# PCB_2_0_4.net
KiCad netlist of a schematic drawn in EAGLE
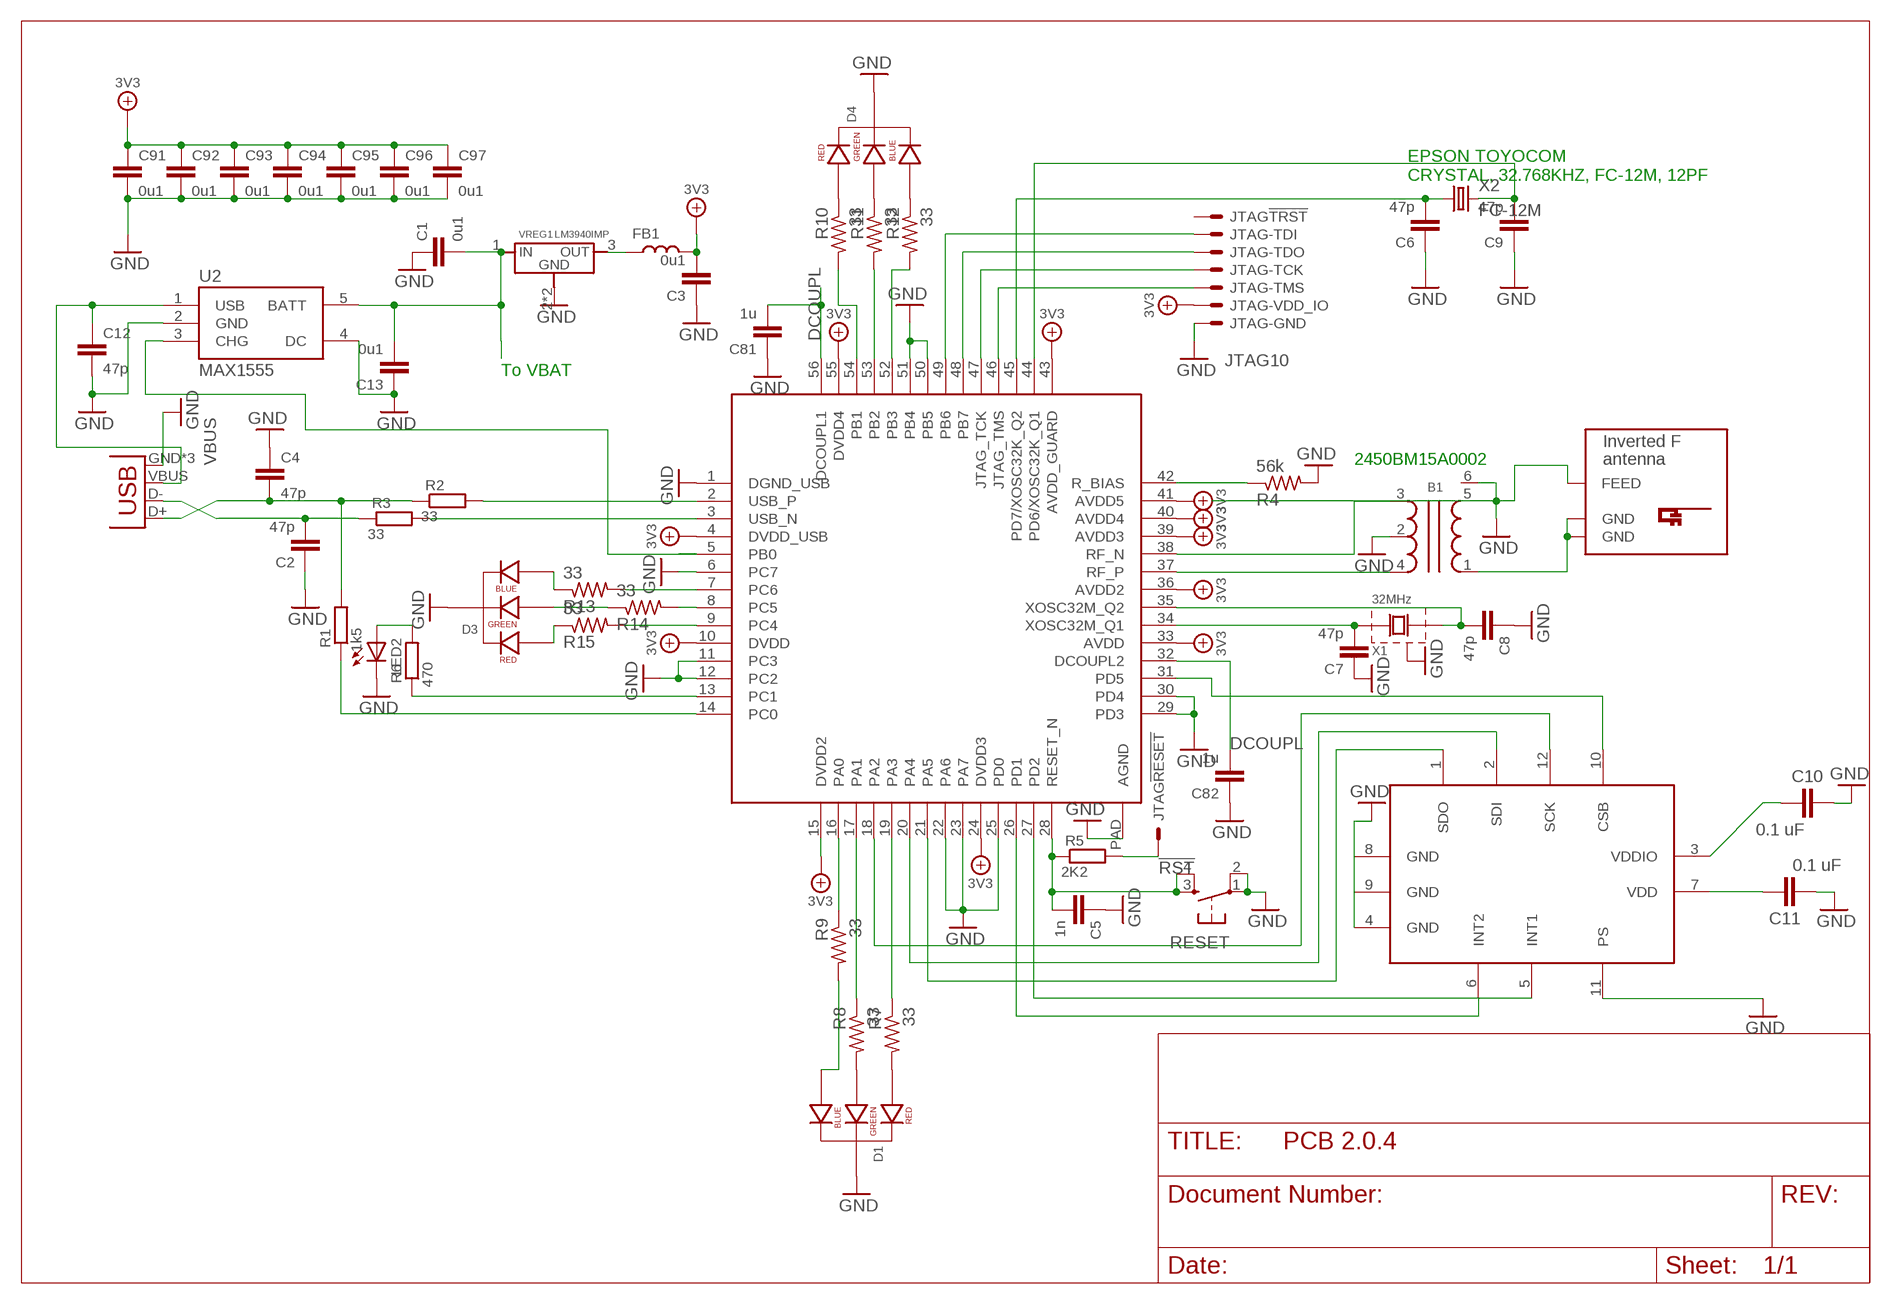
[diagram p0: schematic, sheet 1]

(export (version "E")
  (design (tool "Eeschema 10.0.6"))
  (components
    (comp (ref "B1")
      (value "BALUN")
      (footprint "eagle-import:BALUN-0805")
      (libsource (lib "eagle-import") (part "BALUN"))
    )
    (comp (ref "C1")
      (value "0u1")
      (footprint "eagle-import:C1206")
      (libsource (lib "eagle-import") (part "CC1206"))
    )
    (comp (ref "C2")
      (value "47p")
      (footprint "eagle-import:C0603")
      (libsource (lib "eagle-import") (part "CC0603"))
    )
    (comp (ref "C3")
      (value "0u1")
      (footprint "eagle-import:C1206")
      (libsource (lib "eagle-import") (part "CC1206"))
    )
    (comp (ref "C4")
      (value "47p")
      (footprint "eagle-import:C0603")
      (libsource (lib "eagle-import") (part "CC0603"))
    )
    (comp (ref "C5")
      (value "1n")
      (footprint "eagle-import:C0603")
      (libsource (lib "eagle-import") (part "CC0603"))
    )
    (comp (ref "C6")
      (value "47p")
      (footprint "eagle-import:C0603")
      (libsource (lib "eagle-import") (part "CC0603"))
    )
    (comp (ref "C7")
      (value "47p")
      (footprint "eagle-import:C0603")
      (libsource (lib "eagle-import") (part "CC0603"))
    )
    (comp (ref "C8")
      (value "47p")
      (footprint "eagle-import:C0603")
      (libsource (lib "eagle-import") (part "CC0603"))
    )
    (comp (ref "C9")
      (value "47p")
      (footprint "eagle-import:C0603")
      (libsource (lib "eagle-import") (part "CC0603"))
    )
    (comp (ref "C10")
      (value "0.1 uF")
      (footprint "eagle-import:C0402")
      (libsource (lib "eagle-import") (part "C-EUC0402"))
    )
    (comp (ref "C11")
      (value "0.1 uF")
      (footprint "eagle-import:C0402")
      (libsource (lib "eagle-import") (part "C-EUC0402"))
    )
    (comp (ref "C12")
      (value "47p")
      (footprint "eagle-import:C0603")
      (libsource (lib "eagle-import") (part "CC0603"))
    )
    (comp (ref "C13")
      (value "0u1")
      (footprint "eagle-import:C1206")
      (libsource (lib "eagle-import") (part "CC1206"))
    )
    (comp (ref "C81")
      (value "1u")
      (footprint "eagle-import:C0402")
      (libsource (lib "eagle-import") (part "CC0402"))
    )
    (comp (ref "C82")
      (value "1u")
      (footprint "eagle-import:C0402")
      (libsource (lib "eagle-import") (part "CC0402"))
    )
    (comp (ref "C91")
      (value "0u1")
      (footprint "eagle-import:C0402")
      (libsource (lib "eagle-import") (part "CC0402"))
    )
    (comp (ref "C92")
      (value "0u1")
      (footprint "eagle-import:C0402")
      (libsource (lib "eagle-import") (part "CC0402"))
    )
    (comp (ref "C93")
      (value "0u1")
      (footprint "eagle-import:C0402")
      (libsource (lib "eagle-import") (part "CC0402"))
    )
    (comp (ref "C94")
      (value "0u1")
      (footprint "eagle-import:C0402")
      (libsource (lib "eagle-import") (part "CC0402"))
    )
    (comp (ref "C95")
      (value "0u1")
      (footprint "eagle-import:C0402")
      (libsource (lib "eagle-import") (part "CC0402"))
    )
    (comp (ref "C96")
      (value "0u1")
      (footprint "eagle-import:C0402")
      (libsource (lib "eagle-import") (part "CC0402"))
    )
    (comp (ref "C97")
      (value "0u1")
      (footprint "eagle-import:C0402")
      (libsource (lib "eagle-import") (part "CC0402"))
    )
    (comp (ref "D1")
      (value "LED-RGB-CC-THRUCLEAR")
      (footprint "eagle-import:LED-RGB-THRU")
      (libsource (lib "eagle-import") (part "LED-RGB-CC-THRUCLEAR"))
    )
    (comp (ref "D3")
      (value "LED-RGB-CC-THRUCLEAR")
      (footprint "eagle-import:LED-RGB-THRU")
      (libsource (lib "eagle-import") (part "LED-RGB-CC-THRUCLEAR"))
    )
    (comp (ref "D4")
      (value "LED-RGB-CC-THRUCLEAR")
      (footprint "eagle-import:LED-RGB-THRU")
      (libsource (lib "eagle-import") (part "LED-RGB-CC-THRUCLEAR"))
    )
    (comp (ref "FB1")
      (value "L0603")
      (footprint "eagle-import:R603")
      (libsource (lib "eagle-import") (part "L0603"))
    )
    (comp (ref "JP1")
      (value "USB-MICROB")
      (footprint "eagle-import:USB-MICROB")
      (libsource (lib "eagle-import") (part "USB-MICROB"))
    )
    (comp (ref "JTAG")
      (value "JTAG10")
      (footprint "eagle-import:HDR-2X5-2.00")
      (libsource (lib "eagle-import") (part "JTAG10"))
    )
    (comp (ref "LED2")
      (value "LED805")
      (footprint "eagle-import:LED-805")
      (libsource (lib "eagle-import") (part "LED805"))
    )
    (comp (ref "R1")
      (value "1k5")
      (footprint "eagle-import:R603")
      (libsource (lib "eagle-import") (part "RR603"))
    )
    (comp (ref "R2")
      (value "33")
      (footprint "eagle-import:R603")
      (libsource (lib "eagle-import") (part "RR603"))
    )
    (comp (ref "R3")
      (value "33")
      (footprint "eagle-import:R603")
      (libsource (lib "eagle-import") (part "RR603"))
    )
    (comp (ref "R4")
      (value "56k")
      (footprint "eagle-import:R0402")
      (libsource (lib "eagle-import") (part "R-US_R0402"))
    )
    (comp (ref "R5")
      (value "2K2")
      (footprint "eagle-import:R603")
      (libsource (lib "eagle-import") (part "RR603"))
    )
    (comp (ref "R6")
      (value "470")
      (footprint "eagle-import:R603")
      (libsource (lib "eagle-import") (part "RR603"))
    )
    (comp (ref "R7")
      (value "33")
      (footprint "eagle-import:R0402")
      (libsource (lib "eagle-import") (part "R-US_R0402"))
    )
    (comp (ref "R8")
      (value "33")
      (footprint "eagle-import:R0402")
      (libsource (lib "eagle-import") (part "R-US_R0402"))
    )
    (comp (ref "R9")
      (value "33")
      (footprint "eagle-import:R0402")
      (libsource (lib "eagle-import") (part "R-US_R0402"))
    )
    (comp (ref "R10")
      (value "33")
      (footprint "eagle-import:R0402")
      (libsource (lib "eagle-import") (part "R-US_R0402"))
    )
    (comp (ref "R11")
      (value "33")
      (footprint "eagle-import:R0402")
      (libsource (lib "eagle-import") (part "R-US_R0402"))
    )
    (comp (ref "R12")
      (value "33")
      (footprint "eagle-import:R0402")
      (libsource (lib "eagle-import") (part "R-US_R0402"))
    )
    (comp (ref "R13")
      (value "33")
      (footprint "eagle-import:R0402")
      (libsource (lib "eagle-import") (part "R-US_R0402"))
    )
    (comp (ref "R14")
      (value "33")
      (footprint "eagle-import:R0402")
      (libsource (lib "eagle-import") (part "R-US_R0402"))
    )
    (comp (ref "R15")
      (value "33")
      (footprint "eagle-import:R0402")
      (libsource (lib "eagle-import") (part "R-US_R0402"))
    )
    (comp (ref "RESET")
      (value "TAC_SWITCHSMD")
      (footprint "eagle-import:TACTILE_SWITCH_SMD")
      (libsource (lib "eagle-import") (part "TAC_SWITCHSMD"))
    )
    (comp (ref "U$1")
      (value "BMA250")
      (footprint "eagle-import:12LGA_VGG3-D")
      (libsource (lib "eagle-import") (part "BMA250"))
    )
    (comp (ref "U$2")
      (value "INVERTED_F_ANTENNA+0")
      (footprint "eagle-import:DN007+0")
      (libsource (lib "eagle-import") (part "INVERTED_F_ANTENNA+0"))
    )
    (comp (ref "U1")
      (value "CC2538")
      (footprint "eagle-import:QFN56")
      (libsource (lib "eagle-import") (part "CC2538"))
    )
    (comp (ref "U2")
      (value "MAX1555")
      (footprint "eagle-import:SOT23-5")
      (libsource (lib "eagle-import") (part "MAX1555"))
    )
    (comp (ref "VREG1")
      (value "LM3940IMP")
      (footprint "eagle-import:SOT223")
      (libsource (lib "eagle-import") (part "LM3940IMP"))
    )
    (comp (ref "X1")
      (value "32MHz")
      (footprint "eagle-import:XTAL-4-3225")
      (libsource (lib "eagle-import") (part "XTAL-43225"))
    )
    (comp (ref "X2")
      (value "FC-12M")
      (footprint "eagle-import:FC-12M")
      (libsource (lib "eagle-import") (part "FC-12M"))
    )
  )
  (nets
    (net (code "1") (name "/DCOUPL") (class "Default")
      (node (ref "C81") (pin "2") (pinfunction "2_2") (pintype "passive"))
      (node (ref "C82") (pin "2") (pinfunction "2_2") (pintype "passive"))
      (node (ref "U1") (pin "32") (pinfunction "DCOUPL2_32") (pintype "bidirectional"))
      (node (ref "U1") (pin "56") (pinfunction "DCOUPL1_56") (pintype "bidirectional"))
    )
    (net (code "2") (name "/VBUS") (class "Default")
      (node (ref "C12") (pin "1") (pinfunction "1_1") (pintype "passive"))
      (node (ref "JP1") (pin "VBUS") (pinfunction "VBUS_VBUS") (pintype "bidirectional"))
      (node (ref "U2") (pin "1") (pinfunction "USB_1") (pintype "bidirectional"))
    )
    (net (code "3") (name "/~{RST}") (class "Default")
      (node (ref "JTAG") (pin "4") (pinfunction "S_4") (pintype "passive"))
      (node (ref "R5") (pin "2") (pinfunction "2_2") (pintype "passive"))
    )
    (net (code "4") (name "3V3") (class "Default")
      (node (ref "C3") (pin "2") (pinfunction "2_2") (pintype "passive"))
      (node (ref "C91") (pin "1") (pinfunction "1_1") (pintype "passive"))
      (node (ref "C92") (pin "1") (pinfunction "1_1") (pintype "passive"))
      (node (ref "C93") (pin "1") (pinfunction "1_1") (pintype "passive"))
      (node (ref "C94") (pin "1") (pinfunction "1_1") (pintype "passive"))
      (node (ref "C95") (pin "1") (pinfunction "1_1") (pintype "passive"))
      (node (ref "C96") (pin "1") (pinfunction "1_1") (pintype "passive"))
      (node (ref "C97") (pin "1") (pinfunction "1_1") (pintype "passive"))
      (node (ref "FB1") (pin "2") (pinfunction "P$2_2") (pintype "bidirectional"))
      (node (ref "JTAG") (pin "1") (pinfunction "S_1") (pintype "passive"))
      (node (ref "JTAG") (pin "2") (pinfunction "S_2") (pintype "passive"))
      (node (ref "U1") (pin "10") (pinfunction "DVDD_10") (pintype "bidirectional"))
      (node (ref "U1") (pin "15") (pinfunction "DVDD2_15") (pintype "bidirectional"))
      (node (ref "U1") (pin "24") (pinfunction "DVDD3_24") (pintype "bidirectional"))
      (node (ref "U1") (pin "33") (pinfunction "AVDD_33") (pintype "bidirectional"))
      (node (ref "U1") (pin "36") (pinfunction "AVDD2_36") (pintype "bidirectional"))
      (node (ref "U1") (pin "39") (pinfunction "AVDD3_39") (pintype "bidirectional"))
      (node (ref "U1") (pin "4") (pinfunction "DVDD_USB_4") (pintype "bidirectional"))
      (node (ref "U1") (pin "40") (pinfunction "AVDD4_40") (pintype "bidirectional"))
      (node (ref "U1") (pin "41") (pinfunction "AVDD5_41") (pintype "bidirectional"))
      (node (ref "U1") (pin "43") (pinfunction "AVDD_GUARD_43") (pintype "bidirectional"))
      (node (ref "U1") (pin "55") (pinfunction "DVDD4_55") (pintype "bidirectional"))
    )
    (net (code "5") (name "GND") (class "Default")
      (node (ref "B1") (pin "2") (pinfunction "2_2") (pintype "bidirectional"))
      (node (ref "B1") (pin "5") (pinfunction "5_5") (pintype "bidirectional"))
      (node (ref "B1") (pin "6") (pinfunction "6_6") (pintype "bidirectional"))
      (node (ref "C1") (pin "1") (pinfunction "1_1") (pintype "passive"))
      (node (ref "C10") (pin "1") (pinfunction "1_1") (pintype "passive"))
      (node (ref "C11") (pin "2") (pinfunction "2_2") (pintype "passive"))
      (node (ref "C12") (pin "2") (pinfunction "2_2") (pintype "passive"))
      (node (ref "C13") (pin "1") (pinfunction "1_1") (pintype "passive"))
      (node (ref "C2") (pin "1") (pinfunction "1_1") (pintype "passive"))
      (node (ref "C3") (pin "1") (pinfunction "1_1") (pintype "passive"))
      (node (ref "C4") (pin "1") (pinfunction "1_1") (pintype "passive"))
      (node (ref "C5") (pin "1") (pinfunction "1_1") (pintype "passive"))
      (node (ref "C6") (pin "1") (pinfunction "1_1") (pintype "passive"))
      (node (ref "C7") (pin "1") (pinfunction "1_1") (pintype "passive"))
      (node (ref "C8") (pin "1") (pinfunction "1_1") (pintype "passive"))
      (node (ref "C81") (pin "1") (pinfunction "1_1") (pintype "passive"))
      (node (ref "C82") (pin "1") (pinfunction "1_1") (pintype "passive"))
      (node (ref "C9") (pin "1") (pinfunction "1_1") (pintype "passive"))
      (node (ref "C91") (pin "2") (pinfunction "2_2") (pintype "passive"))
      (node (ref "C92") (pin "2") (pinfunction "2_2") (pintype "passive"))
      (node (ref "C93") (pin "2") (pinfunction "2_2") (pintype "passive"))
      (node (ref "C94") (pin "2") (pinfunction "2_2") (pintype "passive"))
      (node (ref "C95") (pin "2") (pinfunction "2_2") (pintype "passive"))
      (node (ref "C96") (pin "2") (pinfunction "2_2") (pintype "passive"))
      (node (ref "C97") (pin "2") (pinfunction "2_2") (pintype "passive"))
      (node (ref "D1") (pin "2") (pinfunction "CATHODE_2") (pintype "bidirectional"))
      (node (ref "D3") (pin "2") (pinfunction "CATHODE_2") (pintype "bidirectional"))
      (node (ref "D4") (pin "2") (pinfunction "CATHODE_2") (pintype "bidirectional"))
      (node (ref "JP1") (pin "GND") (pinfunction "GND_GND") (pintype "bidirectional"))
      (node (ref "JP1") (pin "MT1") (pinfunction "GND_MT1") (pintype "bidirectional"))
      (node (ref "JP1") (pin "MT2") (pinfunction "GND_MT2") (pintype "bidirectional"))
      (node (ref "JTAG") (pin "10") (pinfunction "S_10") (pintype "passive"))
      (node (ref "JTAG") (pin "8") (pinfunction "S_8") (pintype "passive"))
      (node (ref "LED2") (pin "C") (pinfunction "C_C") (pintype "passive"))
      (node (ref "R4") (pin "2") (pinfunction "2_2") (pintype "passive"))
      (node (ref "RESET") (pin "1") (pinfunction "1_1") (pintype "passive"))
      (node (ref "RESET") (pin "2") (pinfunction "2_2") (pintype "passive"))
      (node (ref "U$1") (pin "11") (pinfunction "PS_11") (pintype "bidirectional"))
      (node (ref "U$1") (pin "4") (pinfunction "GND_4") (pintype "bidirectional"))
      (node (ref "U$1") (pin "8") (pinfunction "GND_8") (pintype "bidirectional"))
      (node (ref "U$1") (pin "9") (pinfunction "GND_9") (pintype "bidirectional"))
      (node (ref "U$2") (pin "FEED") (pinfunction "FEED_FEED") (pintype "bidirectional"))
      (node (ref "U1") (pin "1") (pinfunction "DGND_USB_1") (pintype "bidirectional"))
      (node (ref "U1") (pin "11") (pinfunction "PC3_11") (pintype "bidirectional"))
      (node (ref "U1") (pin "12") (pinfunction "PC2_12") (pintype "bidirectional"))
      (node (ref "U1") (pin "22") (pinfunction "PA6_22") (pintype "bidirectional"))
      (node (ref "U1") (pin "23") (pinfunction "PA7_23") (pintype "bidirectional"))
      (node (ref "U1") (pin "25") (pinfunction "PD0_25") (pintype "bidirectional"))
      (node (ref "U1") (pin "29") (pinfunction "PD3_29") (pintype "bidirectional"))
      (node (ref "U1") (pin "30") (pinfunction "PD4_30") (pintype "bidirectional"))
      (node (ref "U1") (pin "50") (pinfunction "PB5_50") (pintype "bidirectional"))
      (node (ref "U1") (pin "51") (pinfunction "PB4_51") (pintype "bidirectional"))
      (node (ref "U1") (pin "6") (pinfunction "PC7_6") (pintype "bidirectional"))
      (node (ref "U1") (pin "PAD") (pinfunction "AGND_PAD") (pintype "bidirectional"))
      (node (ref "U2") (pin "2") (pinfunction "GND_2") (pintype "bidirectional"))
      (node (ref "U2") (pin "4") (pinfunction "DC_4") (pintype "bidirectional"))
      (node (ref "VREG1") (pin "2") (pinfunction "GND_2") (pintype "bidirectional"))
      (node (ref "VREG1") (pin "4") (pinfunction "GND_4") (pintype "bidirectional"))
      (node (ref "X1") (pin "2") (pinfunction "GND1_2") (pintype "bidirectional"))
      (node (ref "X1") (pin "4") (pinfunction "GND1_4") (pintype "bidirectional"))
    )
    (net (code "6") (name "Net-(B1-Pad1)") (class "Default")
      (node (ref "B1") (pin "1") (pinfunction "1_1") (pintype "bidirectional"))
      (node (ref "U$2") (pin "GND") (pinfunction "GND_GND") (pintype "bidirectional"))
      (node (ref "U$2") (pin "GND@1") (pinfunction "GND_GND@1") (pintype "bidirectional"))
    )
    (net (code "7") (name "Net-(C2-Pad2)") (class "Default")
      (node (ref "C2") (pin "2") (pinfunction "2_2") (pintype "passive"))
      (node (ref "JP1") (pin "D-") (pinfunction "D-_D-") (pintype "bidirectional"))
      (node (ref "R3") (pin "1") (pinfunction "1_1") (pintype "passive"))
    )
    (net (code "8") (name "Net-(C4-Pad2)") (class "Default")
      (node (ref "C4") (pin "2") (pinfunction "2_2") (pintype "passive"))
      (node (ref "JP1") (pin "D+") (pinfunction "D+_D+") (pintype "bidirectional"))
      (node (ref "R1") (pin "2") (pinfunction "2_2") (pintype "passive"))
      (node (ref "R2") (pin "1") (pinfunction "1_1") (pintype "passive"))
    )
    (net (code "9") (name "Net-(D1-BLUE_CATHODE)") (class "Default")
      (node (ref "D1") (pin "4") (pinfunction "BLUE_CATHODE_4") (pintype "bidirectional"))
      (node (ref "R9") (pin "2") (pinfunction "2_2") (pintype "passive"))
    )
    (net (code "10") (name "Net-(D1-GREEN_CATHODE)") (class "Default")
      (node (ref "D1") (pin "3") (pinfunction "GREEN_CATHODE_3") (pintype "bidirectional"))
      (node (ref "R8") (pin "2") (pinfunction "2_2") (pintype "passive"))
    )
    (net (code "11") (name "Net-(D1-RED_CATHODE)") (class "Default")
      (node (ref "D1") (pin "1") (pinfunction "RED_CATHODE_1") (pintype "bidirectional"))
      (node (ref "R7") (pin "2") (pinfunction "2_2") (pintype "passive"))
    )
    (net (code "12") (name "Net-(D3-BLUE_CATHODE)") (class "Default")
      (node (ref "D3") (pin "4") (pinfunction "BLUE_CATHODE_4") (pintype "bidirectional"))
      (node (ref "R13") (pin "1") (pinfunction "1_1") (pintype "passive"))
    )
    (net (code "13") (name "Net-(D3-GREEN_CATHODE)") (class "Default")
      (node (ref "D3") (pin "3") (pinfunction "GREEN_CATHODE_3") (pintype "bidirectional"))
      (node (ref "R14") (pin "1") (pinfunction "1_1") (pintype "passive"))
    )
    (net (code "14") (name "Net-(D3-RED_CATHODE)") (class "Default")
      (node (ref "D3") (pin "1") (pinfunction "RED_CATHODE_1") (pintype "bidirectional"))
      (node (ref "R15") (pin "1") (pinfunction "1_1") (pintype "passive"))
    )
    (net (code "15") (name "Net-(D4-BLUE_CATHODE)") (class "Default")
      (node (ref "D4") (pin "4") (pinfunction "BLUE_CATHODE_4") (pintype "bidirectional"))
      (node (ref "R12") (pin "1") (pinfunction "1_1") (pintype "passive"))
    )
    (net (code "16") (name "Net-(D4-GREEN_CATHODE)") (class "Default")
      (node (ref "D4") (pin "3") (pinfunction "GREEN_CATHODE_3") (pintype "bidirectional"))
      (node (ref "R11") (pin "1") (pinfunction "1_1") (pintype "passive"))
    )
    (net (code "17") (name "Net-(D4-RED_CATHODE)") (class "Default")
      (node (ref "D4") (pin "1") (pinfunction "RED_CATHODE_1") (pintype "bidirectional"))
      (node (ref "R10") (pin "1") (pinfunction "1_1") (pintype "passive"))
    )
    (net (code "18") (name "Net-(FB1-P$1)") (class "Default")
      (node (ref "FB1") (pin "1") (pinfunction "P$1_1") (pintype "bidirectional"))
      (node (ref "VREG1") (pin "3") (pinfunction "OUT_3") (pintype "bidirectional"))
    )
    (net (code "19") (name "Net-(JTAGD-S)") (class "Default")
      (node (ref "JTAG") (pin "9") (pinfunction "S_9") (pintype "passive"))
      (node (ref "U1") (pin "47") (pinfunction "JTAG_TCK_47") (pintype "bidirectional"))
    )
    (net (code "20") (name "Net-(JTAGE-S)") (class "Default")
      (node (ref "JTAG") (pin "5") (pinfunction "S_5") (pintype "passive"))
      (node (ref "U1") (pin "49") (pinfunction "PB6_49") (pintype "bidirectional"))
    )
    (net (code "21") (name "Net-(JTAGF-S)") (class "Default")
      (node (ref "JTAG") (pin "6") (pinfunction "S_6") (pintype "passive"))
      (node (ref "U1") (pin "48") (pinfunction "PB7_48") (pintype "bidirectional"))
    )
    (net (code "22") (name "Net-(JTAGG-S)") (class "Default")
      (node (ref "JTAG") (pin "7") (pinfunction "S_7") (pintype "passive"))
      (node (ref "U1") (pin "46") (pinfunction "JTAG_TMS_46") (pintype "bidirectional"))
    )
    (net (code "23") (name "Net-(LED2-PadA)") (class "Default")
      (node (ref "LED2") (pin "A") (pinfunction "A_A") (pintype "passive"))
      (node (ref "R6") (pin "2") (pinfunction "2_2") (pintype "passive"))
    )
    (net (code "24") (name "Net-(U$1-CSB)") (class "Default")
      (node (ref "U$1") (pin "10") (pinfunction "CSB_10") (pintype "bidirectional"))
      (node (ref "U1") (pin "31") (pinfunction "PD5_31") (pintype "bidirectional"))
    )
    (net (code "25") (name "Net-(U$1-INT1)") (class "Default")
      (node (ref "U$1") (pin "5") (pinfunction "INT1_5") (pintype "bidirectional"))
      (node (ref "U1") (pin "27") (pinfunction "PD2_27") (pintype "bidirectional"))
    )
    (net (code "26") (name "Net-(U$1-INT2)") (class "Default")
      (node (ref "U$1") (pin "6") (pinfunction "INT2_6") (pintype "bidirectional"))
      (node (ref "U1") (pin "26") (pinfunction "PD1_26") (pintype "bidirectional"))
    )
    (net (code "27") (name "Net-(U$1-SCK)") (class "Default")
      (node (ref "U$1") (pin "12") (pinfunction "SCK_12") (pintype "bidirectional"))
      (node (ref "U1") (pin "18") (pinfunction "PA2_18") (pintype "bidirectional"))
    )
    (net (code "28") (name "Net-(U$1-SDI)") (class "Default")
      (node (ref "U$1") (pin "2") (pinfunction "SDI_2") (pintype "bidirectional"))
      (node (ref "U1") (pin "20") (pinfunction "PA4_20") (pintype "bidirectional"))
    )
    (net (code "29") (name "Net-(U$1-SDO)") (class "Default")
      (node (ref "U$1") (pin "1") (pinfunction "SDO_1") (pintype "bidirectional"))
      (node (ref "U1") (pin "21") (pinfunction "PA5_21") (pintype "bidirectional"))
    )
    (net (code "30") (name "Net-(U$1-VDD)") (class "Default")
      (node (ref "C11") (pin "1") (pinfunction "1_1") (pintype "passive"))
      (node (ref "U$1") (pin "7") (pinfunction "VDD_7") (pintype "bidirectional"))
    )
    (net (code "31") (name "Net-(U$1-VDDIO)") (class "Default")
      (node (ref "C10") (pin "2") (pinfunction "2_2") (pintype "passive"))
      (node (ref "U$1") (pin "3") (pinfunction "VDDIO_3") (pintype "bidirectional"))
    )
    (net (code "32") (name "Net-(U1-PA0)") (class "Default")
      (node (ref "R9") (pin "1") (pinfunction "1_1") (pintype "passive"))
      (node (ref "U1") (pin "16") (pinfunction "PA0_16") (pintype "bidirectional"))
    )
    (net (code "33") (name "Net-(U1-PA1)") (class "Default")
      (node (ref "R8") (pin "1") (pinfunction "1_1") (pintype "passive"))
      (node (ref "U1") (pin "17") (pinfunction "PA1_17") (pintype "bidirectional"))
    )
    (net (code "34") (name "Net-(U1-PA3)") (class "Default")
      (node (ref "R7") (pin "1") (pinfunction "1_1") (pintype "passive"))
      (node (ref "U1") (pin "19") (pinfunction "PA3_19") (pintype "bidirectional"))
    )
    (net (code "35") (name "Net-(U1-PB0)") (class "Default")
      (node (ref "U1") (pin "5") (pinfunction "PB0_5") (pintype "bidirectional"))
      (node (ref "U2") (pin "3") (pinfunction "CHG_3") (pintype "bidirectional"))
    )
    (net (code "36") (name "Net-(U1-PB1)") (class "Default")
      (node (ref "R10") (pin "2") (pinfunction "2_2") (pintype "passive"))
      (node (ref "U1") (pin "54") (pinfunction "PB1_54") (pintype "bidirectional"))
    )
    (net (code "37") (name "Net-(U1-PB2)") (class "Default")
      (node (ref "R11") (pin "2") (pinfunction "2_2") (pintype "passive"))
      (node (ref "U1") (pin "53") (pinfunction "PB2_53") (pintype "bidirectional"))
    )
    (net (code "38") (name "Net-(U1-PB3)") (class "Default")
      (node (ref "R12") (pin "2") (pinfunction "2_2") (pintype "passive"))
      (node (ref "U1") (pin "52") (pinfunction "PB3_52") (pintype "bidirectional"))
    )
    (net (code "39") (name "Net-(U1-PC0)") (class "Default")
      (node (ref "R1") (pin "1") (pinfunction "1_1") (pintype "passive"))
      (node (ref "U1") (pin "14") (pinfunction "PC0_14") (pintype "bidirectional"))
    )
    (net (code "40") (name "Net-(U1-PC1)") (class "Default")
      (node (ref "R6") (pin "1") (pinfunction "1_1") (pintype "passive"))
      (node (ref "U1") (pin "13") (pinfunction "PC1_13") (pintype "bidirectional"))
    )
    (net (code "41") (name "Net-(U1-PC4)") (class "Default")
      (node (ref "R15") (pin "2") (pinfunction "2_2") (pintype "passive"))
      (node (ref "U1") (pin "9") (pinfunction "PC4_9") (pintype "bidirectional"))
    )
    (net (code "42") (name "Net-(U1-PC5)") (class "Default")
      (node (ref "R14") (pin "2") (pinfunction "2_2") (pintype "passive"))
      (node (ref "U1") (pin "8") (pinfunction "PC5_8") (pintype "bidirectional"))
    )
    (net (code "43") (name "Net-(U1-PC6)") (class "Default")
      (node (ref "R13") (pin "2") (pinfunction "2_2") (pintype "passive"))
      (node (ref "U1") (pin "7") (pinfunction "PC6_7") (pintype "bidirectional"))
    )
    (net (code "44") (name "Net-(U1-PD6{slash}XOSC32K_Q1)") (class "Default")
      (node (ref "C9") (pin "2") (pinfunction "2_2") (pintype "passive"))
      (node (ref "U1") (pin "44") (pinfunction "PD6/XOSC32K_Q1_44") (pintype "bidirectional"))
      (node (ref "X2") (pin "2") (pinfunction "2_2") (pintype "passive"))
    )
    (net (code "45") (name "Net-(U1-PD7{slash}XOSC32K_Q2)") (class "Default")
      (node (ref "C6") (pin "2") (pinfunction "2_2") (pintype "passive"))
      (node (ref "U1") (pin "45") (pinfunction "PD7/XOSC32K_Q2_45") (pintype "bidirectional"))
      (node (ref "X2") (pin "1") (pinfunction "1_1") (pintype "passive"))
    )
    (net (code "46") (name "Net-(U1-RESET_N)") (class "Default")
      (node (ref "C5") (pin "2") (pinfunction "2_2") (pintype "passive"))
      (node (ref "R5") (pin "1") (pinfunction "1_1") (pintype "passive"))
      (node (ref "RESET") (pin "3") (pinfunction "3_3") (pintype "passive"))
      (node (ref "RESET") (pin "4") (pinfunction "4_4") (pintype "passive"))
      (node (ref "U1") (pin "28") (pinfunction "RESET_N_28") (pintype "bidirectional"))
    )
    (net (code "47") (name "Net-(U1-RF_N)") (class "Default")
      (node (ref "B1") (pin "3") (pinfunction "3_3") (pintype "bidirectional"))
      (node (ref "U1") (pin "38") (pinfunction "RF_N_38") (pintype "bidirectional"))
    )
    (net (code "48") (name "Net-(U1-RF_P)") (class "Default")
      (node (ref "B1") (pin "4") (pinfunction "4_4") (pintype "bidirectional"))
      (node (ref "U1") (pin "37") (pinfunction "RF_P_37") (pintype "bidirectional"))
    )
    (net (code "49") (name "Net-(U1-R_BIAS)") (class "Default")
      (node (ref "R4") (pin "1") (pinfunction "1_1") (pintype "passive"))
      (node (ref "U1") (pin "42") (pinfunction "R_BIAS_42") (pintype "bidirectional"))
    )
    (net (code "50") (name "Net-(U1-USB_N)") (class "Default")
      (node (ref "R3") (pin "2") (pinfunction "2_2") (pintype "passive"))
      (node (ref "U1") (pin "3") (pinfunction "USB_N_3") (pintype "bidirectional"))
    )
    (net (code "51") (name "Net-(U1-USB_P)") (class "Default")
      (node (ref "R2") (pin "2") (pinfunction "2_2") (pintype "passive"))
      (node (ref "U1") (pin "2") (pinfunction "USB_P_2") (pintype "bidirectional"))
    )
    (net (code "52") (name "Net-(U1-XOSC32M_Q1)") (class "Default")
      (node (ref "C7") (pin "2") (pinfunction "2_2") (pintype "passive"))
      (node (ref "U1") (pin "34") (pinfunction "XOSC32M_Q1_34") (pintype "bidirectional"))
      (node (ref "X1") (pin "1") (pinfunction "X1_1") (pintype "bidirectional"))
    )
    (net (code "53") (name "Net-(U1-XOSC32M_Q2)") (class "Default")
      (node (ref "C8") (pin "2") (pinfunction "2_2") (pintype "passive"))
      (node (ref "U1") (pin "35") (pinfunction "XOSC32M_Q2_35") (pintype "bidirectional"))
      (node (ref "X1") (pin "3") (pinfunction "X2_3") (pintype "bidirectional"))
    )
    (net (code "54") (name "Net-(U2-BATT)") (class "Default")
      (node (ref "C1") (pin "2") (pinfunction "2_2") (pintype "passive"))
      (node (ref "C13") (pin "2") (pinfunction "2_2") (pintype "passive"))
      (node (ref "U2") (pin "5") (pinfunction "BATT_5") (pintype "bidirectional"))
      (node (ref "VREG1") (pin "1") (pinfunction "IN_1") (pintype "bidirectional"))
    )
    (net (code "55") (name "unconnected-(JTAGB-S-Pad3)") (class "Default")
      (node (ref "JTAG") (pin "3") (pinfunction "S_3") (pintype "passive"))
    )
  )
)
